# nfc-epd-sensors.net
KiCad netlist of a schematic drawn in Altium Designer
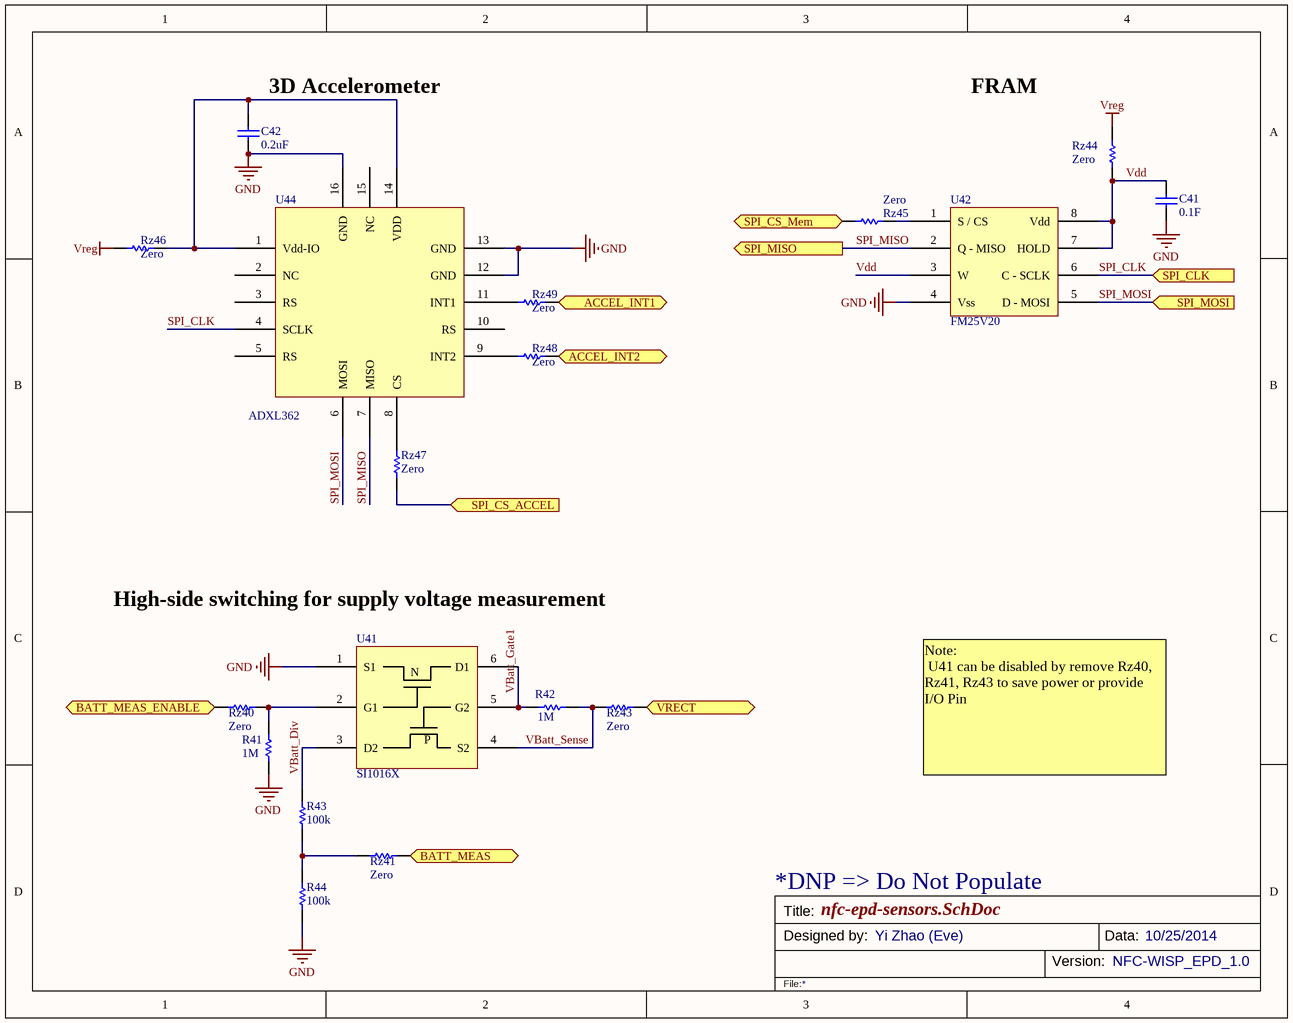
[diagram p0: nfc-epd-sensors.SchDoc]

(export (version "E")
  (design (tool "Eeschema 10.0.6"))
  (components
    (comp (ref "C41")
      (value "0.1F")
      (footprint "0603")
      (description "Ceramic Capacitor (Surface Mount)")
      (fields (field (name "MANUFACTURER") "Generic Ceramic Chip Cap (TBD)") (field (name "Comment") "Cap"))
      (libsource (lib "WISP_AD10") (part "Cap"))
    )
    (comp (ref "C42")
      (value "0.2uF")
      (footprint "0402")
      (description "Ceramic Capacitor (Surface Mount)")
      (fields (field (name "MANUFACTURER") "Generic Ceramic Chip Cap (TBD)") (field (name "Comment") "Cap"))
      (libsource (lib "WISP_US") (part "Cap"))
    )
    (comp (ref "R41")
      (value "1M")
      (footprint "0603")
      (description "Chip Resistor (Surface Mount)")
      (fields (field (name "MANUFACTURER") "Generic Chip Res (TBD)") (field (name "Comment") "Res"))
      (libsource (lib "WISP_AD10") (part "Res"))
    )
    (comp (ref "R42")
      (value "1M")
      (footprint "0603")
      (description "Chip Resistor (Surface Mount)")
      (fields (field (name "MANUFACTURER") "Generic Chip Res (TBD)") (field (name "Comment") "Res"))
      (libsource (lib "WISP_AD10") (part "Res"))
    )
    (comp (ref "R43")
      (value "100k")
      (footprint "0603")
      (description "Chip Resistor (Surface Mount)")
      (fields (field (name "MANUFACTURER") "Generic Chip Res (TBD)") (field (name "Comment") "Res"))
      (libsource (lib "WISP_AD10") (part "Res"))
    )
    (comp (ref "R44")
      (value "100k")
      (footprint "0603")
      (description "Chip Resistor (Surface Mount)")
      (fields (field (name "MANUFACTURER") "Generic Chip Res (TBD)") (field (name "Comment") "Res"))
      (libsource (lib "WISP_AD10") (part "Res"))
    )
    (comp (ref "Rz40")
      (value "Zero")
      (footprint "0603")
      (description "Chip Resistor (Surface Mount)")
      (fields
        (field (name "MANUFACTURER") "Generic Chip Res (TBD)")
        (field (name "MANUFACTURER PART NUMBER") "RC0603FR-070RL")
      )
      (libsource (lib "WREL_AD10") (part "Res"))
    )
    (comp (ref "Rz41")
      (value "Zero")
      (footprint "0603")
      (description "Chip Resistor (Surface Mount)")
      (fields
        (field (name "MANUFACTURER") "Generic Chip Res (TBD)")
        (field (name "MANUFACTURER PART NUMBER") "RC0603FR-070RL")
      )
      (libsource (lib "WREL_AD10") (part "Res"))
    )
    (comp (ref "Rz43")
      (value "Zero")
      (footprint "0603")
      (description "Chip Resistor (Surface Mount)")
      (fields
        (field (name "MANUFACTURER") "Generic Chip Res (TBD)")
        (field (name "MANUFACTURER PART NUMBER") "RC0603FR-070RL")
      )
      (libsource (lib "WREL_AD10") (part "Res"))
    )
    (comp (ref "Rz44")
      (value "Zero")
      (footprint "0603")
      (description "Chip Resistor (Surface Mount)")
      (fields
        (field (name "MANUFACTURER") "Generic Chip Res (TBD)")
        (field (name "MANUFACTURER PART NUMBER") "RC0603FR-070RL")
      )
      (libsource (lib "WREL_AD10") (part "Res"))
    )
    (comp (ref "Rz45")
      (value "Zero")
      (footprint "0603")
      (description "Chip Resistor (Surface Mount)")
      (fields
        (field (name "MANUFACTURER") "Generic Chip Res (TBD)")
        (field (name "MANUFACTURER PART NUMBER") "RC0603FR-070RL")
      )
      (libsource (lib "WREL_AD10") (part "Res"))
    )
    (comp (ref "Rz46")
      (value "Zero")
      (footprint "0603")
      (description "Chip Resistor (Surface Mount)")
      (fields
        (field (name "MANUFACTURER") "Generic Chip Res (TBD)")
        (field (name "MANUFACTURER PART NUMBER") "RC0603FR-070RL")
      )
      (libsource (lib "WREL_AD10") (part "Res"))
    )
    (comp (ref "Rz47")
      (value "Zero")
      (footprint "0603")
      (description "Chip Resistor (Surface Mount)")
      (fields
        (field (name "MANUFACTURER") "Generic Chip Res (TBD)")
        (field (name "MANUFACTURER PART NUMBER") "RC0603FR-070RL")
      )
      (libsource (lib "WREL_AD10") (part "Res"))
    )
    (comp (ref "Rz48")
      (value "Zero")
      (footprint "0603")
      (description "Chip Resistor (Surface Mount)")
      (fields
        (field (name "MANUFACTURER") "Generic Chip Res (TBD)")
        (field (name "MANUFACTURER PART NUMBER") "RC0603FR-070RL")
      )
      (libsource (lib "WREL_AD10") (part "Res"))
    )
    (comp (ref "Rz49")
      (value "Zero")
      (footprint "0603")
      (description "Chip Resistor (Surface Mount)")
      (fields
        (field (name "MANUFACTURER") "Generic Chip Res (TBD)")
        (field (name "MANUFACTURER PART NUMBER") "RC0603FR-070RL")
      )
      (libsource (lib "WREL_AD10") (part "Res"))
    )
    (comp (ref "U41")
      (value "SI1016X")
      (footprint "SC-89-6 Vishay")
      (description "NMOS and PMOS array")
      (fields
        (field (name "MANUFACTURER") "Vishay Siliconix")
        (field (name "MANUFACTURER PART NUMBER") "SI1016X-T1-GE3")
      )
      (libsource (lib "WISP_AD10") (part "SI1016X"))
    )
    (comp (ref "U42")
      (value "FM25V20")
      (footprint "TDFN-8")
      (description "? Mbit FRAM SPI")
      (fields
        (field (name "DIGI-KEY PART NUMBER") "428-3214-ND")
        (field (name "MANUFACTURER") "Cypress Semiconductor Corp")
      )
      (libsource (lib "WISP_AD10") (part "FM25V20"))
    )
    (comp (ref "U44")
      (value "ADXL362")
      (footprint "ADXL362 - Mod 6mil clearence")
      (description "3D ACCEL DIG LO PWR 16LGA")
      (fields
        (field (name "DIGI-KEY PART NUMBER") "ADXL362BCCZ-R2CT-ND")
        (field (name "MANUFACTURER") "Analog Devices Inc")
      )
      (libsource (lib "WISP_AD10") (part "ADXL362"))
    )
  )
  (nets
    (net (code "1") (name "/ACCEL_INT1") (class "Default")
      (node (ref "Rz49") (pin "2") (pinfunction "2_2") (pintype "passive"))
    )
    (net (code "2") (name "/ACCEL_INT2") (class "Default")
      (node (ref "Rz48") (pin "2") (pinfunction "2_2") (pintype "passive"))
    )
    (net (code "3") (name "/BATT_MEAS") (class "Default")
      (node (ref "Rz41") (pin "1") (pinfunction "1_1") (pintype "passive"))
    )
    (net (code "4") (name "/BATT_MEAS_ENABLE") (class "Default")
      (node (ref "Rz40") (pin "2") (pinfunction "2_2") (pintype "passive"))
    )
    (net (code "5") (name "/SPI_CLK") (class "Default")
      (node (ref "U42") (pin "6") (pinfunction "C_-_SCLK_6") (pintype "passive"))
      (node (ref "U44") (pin "4") (pinfunction "SCLK_4") (pintype "passive"))
    )
    (net (code "6") (name "/SPI_CS_ACCEL") (class "Default")
      (node (ref "Rz47") (pin "1") (pinfunction "1_1") (pintype "passive"))
    )
    (net (code "7") (name "/SPI_CS_Mem") (class "Default")
      (node (ref "Rz45") (pin "1") (pinfunction "1_1") (pintype "passive"))
    )
    (net (code "8") (name "/SPI_MISO") (class "Default")
      (node (ref "U42") (pin "2") (pinfunction "Q_-_MISO_2") (pintype "passive"))
      (node (ref "U44") (pin "7") (pinfunction "MISO_7") (pintype "passive"))
    )
    (net (code "9") (name "/SPI_MOSI") (class "Default")
      (node (ref "U42") (pin "5") (pinfunction "D_-_MOSI_5") (pintype "passive"))
      (node (ref "U44") (pin "6") (pinfunction "MOSI_6") (pintype "passive"))
    )
    (net (code "10") (name "/VBatt_Div") (class "Default")
      (node (ref "R43") (pin "2") (pinfunction "2_2") (pintype "passive"))
      (node (ref "U41") (pin "3") (pinfunction "D2_3") (pintype "passive"))
    )
    (net (code "11") (name "/VBatt_Gate1") (class "Default")
      (node (ref "R42") (pin "2") (pinfunction "2_2") (pintype "passive"))
      (node (ref "U41") (pin "5") (pinfunction "G2_5") (pintype "passive"))
      (node (ref "U41") (pin "6") (pinfunction "D1_6") (pintype "passive"))
    )
    (net (code "12") (name "/VBatt_Sense") (class "Default")
      (node (ref "R42") (pin "1") (pinfunction "1_1") (pintype "passive"))
      (node (ref "Rz43") (pin "2") (pinfunction "2_2") (pintype "passive"))
      (node (ref "U41") (pin "4") (pinfunction "S2_4") (pintype "passive"))
    )
    (net (code "13") (name "/VRECT") (class "Default")
      (node (ref "Rz43") (pin "1") (pinfunction "1_1") (pintype "passive"))
    )
    (net (code "14") (name "/Vdd") (class "Default")
      (node (ref "C41") (pin "2") (pinfunction "2_2") (pintype "passive"))
      (node (ref "Rz44") (pin "2") (pinfunction "2_2") (pintype "passive"))
      (node (ref "U42") (pin "3") (pinfunction "W_3") (pintype "passive"))
      (node (ref "U42") (pin "7") (pinfunction "HOLD_7") (pintype "passive"))
      (node (ref "U42") (pin "8") (pinfunction "Vdd_8") (pintype "passive"))
    )
    (net (code "15") (name "GND") (class "Default")
      (node (ref "C41") (pin "1") (pinfunction "1_1") (pintype "passive"))
      (node (ref "C42") (pin "2") (pinfunction "2_2") (pintype "passive"))
      (node (ref "R41") (pin "1") (pinfunction "1_1") (pintype "passive"))
      (node (ref "R44") (pin "1") (pinfunction "1_1") (pintype "passive"))
      (node (ref "U41") (pin "1") (pinfunction "S1_1") (pintype "passive"))
      (node (ref "U42") (pin "4") (pinfunction "Vss_4") (pintype "passive"))
      (node (ref "U44") (pin "12") (pinfunction "GND_12") (pintype "passive"))
      (node (ref "U44") (pin "13") (pinfunction "GND_13") (pintype "passive"))
      (node (ref "U44") (pin "16") (pinfunction "GND_16") (pintype "passive"))
    )
    (net (code "16") (name "Net-(R43-Pad1)") (class "Default")
      (node (ref "R43") (pin "1") (pinfunction "1_1") (pintype "passive"))
      (node (ref "R44") (pin "2") (pinfunction "2_2") (pintype "passive"))
      (node (ref "Rz41") (pin "2") (pinfunction "2_2") (pintype "passive"))
    )
    (net (code "17") (name "Net-(U41-G1)") (class "Default")
      (node (ref "R41") (pin "2") (pinfunction "2_2") (pintype "passive"))
      (node (ref "Rz40") (pin "1") (pinfunction "1_1") (pintype "passive"))
      (node (ref "U41") (pin "2") (pinfunction "G1_2") (pintype "passive"))
    )
    (net (code "18") (name "Net-(U42-S_{slash}_CS)") (class "Default")
      (node (ref "Rz45") (pin "2") (pinfunction "2_2") (pintype "passive"))
      (node (ref "U42") (pin "1") (pinfunction "S_/_CS_1") (pintype "passive"))
    )
    (net (code "19") (name "Net-(U44-CS)") (class "Default")
      (node (ref "Rz47") (pin "2") (pinfunction "2_2") (pintype "passive"))
      (node (ref "U44") (pin "8") (pinfunction "CS_8") (pintype "passive"))
    )
    (net (code "20") (name "Net-(U44-INT1)") (class "Default")
      (node (ref "Rz49") (pin "1") (pinfunction "1_1") (pintype "passive"))
      (node (ref "U44") (pin "11") (pinfunction "INT1_11") (pintype "passive"))
    )
    (net (code "21") (name "Net-(U44-INT2)") (class "Default")
      (node (ref "Rz48") (pin "1") (pinfunction "1_1") (pintype "passive"))
      (node (ref "U44") (pin "9") (pinfunction "INT2_9") (pintype "passive"))
    )
    (net (code "22") (name "Net-(U44-VDD)") (class "Default")
      (node (ref "C42") (pin "1") (pinfunction "1_1") (pintype "passive"))
      (node (ref "Rz46") (pin "2") (pinfunction "2_2") (pintype "passive"))
      (node (ref "U44") (pin "1") (pinfunction "Vdd-IO_1") (pintype "passive"))
      (node (ref "U44") (pin "14") (pinfunction "VDD_14") (pintype "passive"))
    )
    (net (code "23") (name "Vreg") (class "Default")
      (node (ref "Rz44") (pin "1") (pinfunction "1_1") (pintype "passive"))
      (node (ref "Rz46") (pin "1") (pinfunction "1_1") (pintype "passive"))
    )
    (net (code "24") (name "unconnected-(U44-NC-Pad2)") (class "Default")
      (node (ref "U44") (pin "2") (pinfunction "NC_2") (pintype "passive"))
    )
    (net (code "25") (name "unconnected-(U44-NC-Pad15)") (class "Default")
      (node (ref "U44") (pin "15") (pinfunction "NC_15") (pintype "passive"))
    )
    (net (code "26") (name "unconnected-(U44-RS-Pad3)") (class "Default")
      (node (ref "U44") (pin "3") (pinfunction "RS_3") (pintype "passive"))
    )
    (net (code "27") (name "unconnected-(U44-RS-Pad5)") (class "Default")
      (node (ref "U44") (pin "5") (pinfunction "RS_5") (pintype "passive"))
    )
    (net (code "28") (name "unconnected-(U44-RS-Pad10)") (class "Default")
      (node (ref "U44") (pin "10") (pinfunction "RS_10") (pintype "passive"))
    )
  )
)
